# IMX_1_8_V_Interface_Power_Supply.net
KiCad netlist of a schematic drawn in Altium Designer
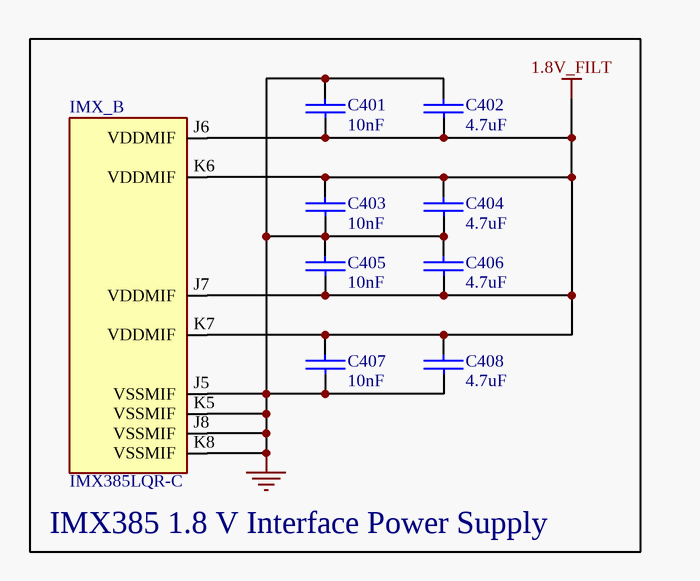
[diagram p0: IMX_1.8 V Interface Power Supply.SchDoc]

(export (version "E")
  (design (tool "Eeschema 10.0.6"))
  (components
    (comp (ref "C401")
      (value "10nF")
      (footprint "Capacitor, 0402")
      (description "Ceramic Capacitor, 16V, 10% +/- Tol, X7R, 10nF, SMD, 0402, #CL05B103KO5NNNC, JLC#C318577")
      (libsource (lib "Component Library") (part "Capacitor, 0402, 10nF"))
    )
    (comp (ref "C402")
      (value "4.7uF")
      (footprint "Capacitor, 0402")
      (description "Ceramic Capacitor, 10V, 10% +/- Tol, X5R, 4.7uF, SMD, 0402, #CL05A475KP5NRNC, JLC#C368809")
      (libsource (lib "Component Library") (part "Capacitor, 0402, 4.7uF"))
    )
    (comp (ref "C403")
      (value "10nF")
      (footprint "Capacitor, 0402")
      (description "Ceramic Capacitor, 16V, 10% +/- Tol, X7R, 10nF, SMD, 0402, #CL05B103KO5NNNC, JLC#C318577")
      (libsource (lib "Component Library") (part "Capacitor, 0402, 10nF"))
    )
    (comp (ref "C404")
      (value "4.7uF")
      (footprint "Capacitor, 0402")
      (description "Ceramic Capacitor, 10V, 10% +/- Tol, X5R, 4.7uF, SMD, 0402, #CL05A475KP5NRNC, JLC#C368809")
      (libsource (lib "Component Library") (part "Capacitor, 0402, 4.7uF"))
    )
    (comp (ref "C405")
      (value "10nF")
      (footprint "Capacitor, 0402")
      (description "Ceramic Capacitor, 16V, 10% +/- Tol, X7R, 10nF, SMD, 0402, #CL05B103KO5NNNC, JLC#C318577")
      (libsource (lib "Component Library") (part "Capacitor, 0402, 10nF"))
    )
    (comp (ref "C406")
      (value "4.7uF")
      (footprint "Capacitor, 0402")
      (description "Ceramic Capacitor, 10V, 10% +/- Tol, X5R, 4.7uF, SMD, 0402, #CL05A475KP5NRNC, JLC#C368809")
      (libsource (lib "Component Library") (part "Capacitor, 0402, 4.7uF"))
    )
    (comp (ref "C407")
      (value "10nF")
      (footprint "Capacitor, 0402")
      (description "Ceramic Capacitor, 16V, 10% +/- Tol, X7R, 10nF, SMD, 0402, #CL05B103KO5NNNC, JLC#C318577")
      (libsource (lib "Component Library") (part "Capacitor, 0402, 10nF"))
    )
    (comp (ref "C408")
      (value "4.7uF")
      (footprint "Capacitor, 0402")
      (description "Ceramic Capacitor, 10V, 10% +/- Tol, X5R, 4.7uF, SMD, 0402, #CL05A475KP5NRNC, JLC#C368809")
      (libsource (lib "Component Library") (part "Capacitor, 0402, 4.7uF"))
    )
    (comp (ref "IMX_")
      (value "IMX385LQR-C")
      (footprint "IMX385LQR")
      (libsource (lib "Component Library") (part "IMX385LQR"))
    )
  )
  (nets
    (net (code "1") (name "1.8V_FILT") (class "Default")
      (node (ref "C401") (pin "2") (pinfunction "2_2") (pintype "passive"))
      (node (ref "C402") (pin "2") (pinfunction "2_2") (pintype "passive"))
      (node (ref "C403") (pin "1") (pinfunction "1_1") (pintype "passive"))
      (node (ref "C404") (pin "1") (pinfunction "1_1") (pintype "passive"))
      (node (ref "C405") (pin "2") (pinfunction "2_2") (pintype "passive"))
      (node (ref "C406") (pin "2") (pinfunction "2_2") (pintype "passive"))
      (node (ref "C407") (pin "1") (pinfunction "1_1") (pintype "passive"))
      (node (ref "C408") (pin "1") (pinfunction "1_1") (pintype "passive"))
      (node (ref "IMX_") (pin "J6") (pinfunction "VDDMIF_J6") (pintype "passive"))
      (node (ref "IMX_") (pin "J7") (pinfunction "VDDMIF_J7") (pintype "passive"))
      (node (ref "IMX_") (pin "K6") (pinfunction "VDDMIF_K6") (pintype "passive"))
      (node (ref "IMX_") (pin "K7") (pinfunction "VDDMIF_K7") (pintype "passive"))
    )
    (net (code "2") (name "GND") (class "Default")
      (node (ref "C401") (pin "1") (pinfunction "1_1") (pintype "passive"))
      (node (ref "C402") (pin "1") (pinfunction "1_1") (pintype "passive"))
      (node (ref "C403") (pin "2") (pinfunction "2_2") (pintype "passive"))
      (node (ref "C404") (pin "2") (pinfunction "2_2") (pintype "passive"))
      (node (ref "C405") (pin "1") (pinfunction "1_1") (pintype "passive"))
      (node (ref "C406") (pin "1") (pinfunction "1_1") (pintype "passive"))
      (node (ref "C407") (pin "2") (pinfunction "2_2") (pintype "passive"))
      (node (ref "C408") (pin "2") (pinfunction "2_2") (pintype "passive"))
      (node (ref "IMX_") (pin "J5") (pinfunction "VSSMIF_J5") (pintype "passive"))
      (node (ref "IMX_") (pin "J8") (pinfunction "VSSMIF_J8") (pintype "passive"))
      (node (ref "IMX_") (pin "K5") (pinfunction "VSSMIF_K5") (pintype "passive"))
      (node (ref "IMX_") (pin "K8") (pinfunction "VSSMIF_K8") (pintype "passive"))
    )
  )
)
